# LED_Breakout_Board.net
KiCad netlist of a schematic drawn in EAGLE
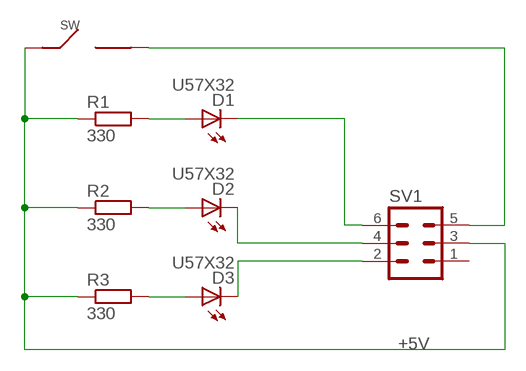
[diagram p0: schematic, sheet 1]

(export (version "E")
  (design (tool "Eeschema 10.0.6"))
  (components
    (comp (ref "D1")
      (value "U57X32")
      (footprint "eagle-import:U57X32")
      (libsource (lib "eagle-import") (part "U57X32"))
    )
    (comp (ref "D2")
      (value "U57X32")
      (footprint "eagle-import:U57X32")
      (libsource (lib "eagle-import") (part "U57X32"))
    )
    (comp (ref "D3")
      (value "U57X32")
      (footprint "eagle-import:U57X32")
      (libsource (lib "eagle-import") (part "U57X32"))
    )
    (comp (ref "R1")
      (value "330")
      (footprint "eagle-import:R3225")
      (libsource (lib "eagle-import") (part "R-EU_R3225"))
    )
    (comp (ref "R2")
      (value "330")
      (footprint "eagle-import:R3225")
      (libsource (lib "eagle-import") (part "R-EU_R3225"))
    )
    (comp (ref "R3")
      (value "330")
      (footprint "eagle-import:R3225")
      (libsource (lib "eagle-import") (part "R-EU_R3225"))
    )
    (comp (ref "SV1")
      (value "MA03-2")
      (footprint "eagle-import:MA03-2")
      (libsource (lib "eagle-import") (part "MA03-2"))
    )
    (comp (ref "SW")
      (value "PUSHBUTTON")
      (footprint "eagle-import:PUSHBUTTON")
      (libsource (lib "eagle-import") (part "PUSHBUTTON"))
    )
  )
  (nets
    (net (code "1") (name "/+5V") (class "Default")
      (node (ref "R1") (pin "1") (pinfunction "1_1") (pintype "passive"))
      (node (ref "R2") (pin "1") (pinfunction "1_1") (pintype "passive"))
      (node (ref "R3") (pin "1") (pinfunction "1_1") (pintype "passive"))
      (node (ref "SV1") (pin "3") (pinfunction "3_3") (pintype "passive"))
      (node (ref "SW") (pin "IN") (pinfunction "IN_IN") (pintype "bidirectional"))
    )
    (net (code "2") (name "Net-(D1-C)") (class "Default")
      (node (ref "D1") (pin "K") (pinfunction "C_K") (pintype "passive"))
      (node (ref "SV1") (pin "6") (pinfunction "6_6") (pintype "passive"))
    )
    (net (code "3") (name "Net-(D1-PadA)") (class "Default")
      (node (ref "D1") (pin "A") (pinfunction "A_A") (pintype "passive"))
      (node (ref "R1") (pin "2") (pinfunction "2_2") (pintype "passive"))
    )
    (net (code "4") (name "Net-(D2-C)") (class "Default")
      (node (ref "D2") (pin "K") (pinfunction "C_K") (pintype "passive"))
      (node (ref "SV1") (pin "4") (pinfunction "4_4") (pintype "passive"))
    )
    (net (code "5") (name "Net-(D2-PadA)") (class "Default")
      (node (ref "D2") (pin "A") (pinfunction "A_A") (pintype "passive"))
      (node (ref "R2") (pin "2") (pinfunction "2_2") (pintype "passive"))
    )
    (net (code "6") (name "Net-(D3-C)") (class "Default")
      (node (ref "D3") (pin "K") (pinfunction "C_K") (pintype "passive"))
      (node (ref "SV1") (pin "2") (pinfunction "2_2") (pintype "passive"))
    )
    (net (code "7") (name "Net-(D3-PadA)") (class "Default")
      (node (ref "D3") (pin "A") (pinfunction "A_A") (pintype "passive"))
      (node (ref "R3") (pin "2") (pinfunction "2_2") (pintype "passive"))
    )
    (net (code "8") (name "Net-(SV1-Pad5)") (class "Default")
      (node (ref "SV1") (pin "5") (pinfunction "5_5") (pintype "passive"))
      (node (ref "SW") (pin "OUT") (pinfunction "OUT_OUT") (pintype "bidirectional"))
    )
    (net (code "9") (name "unconnected-(SV1-Pad1)") (class "Default")
      (node (ref "SV1") (pin "1") (pinfunction "1_1") (pintype "passive"))
    )
  )
)
